# Triggy_0_2.net
KiCad netlist of a schematic drawn in EAGLE
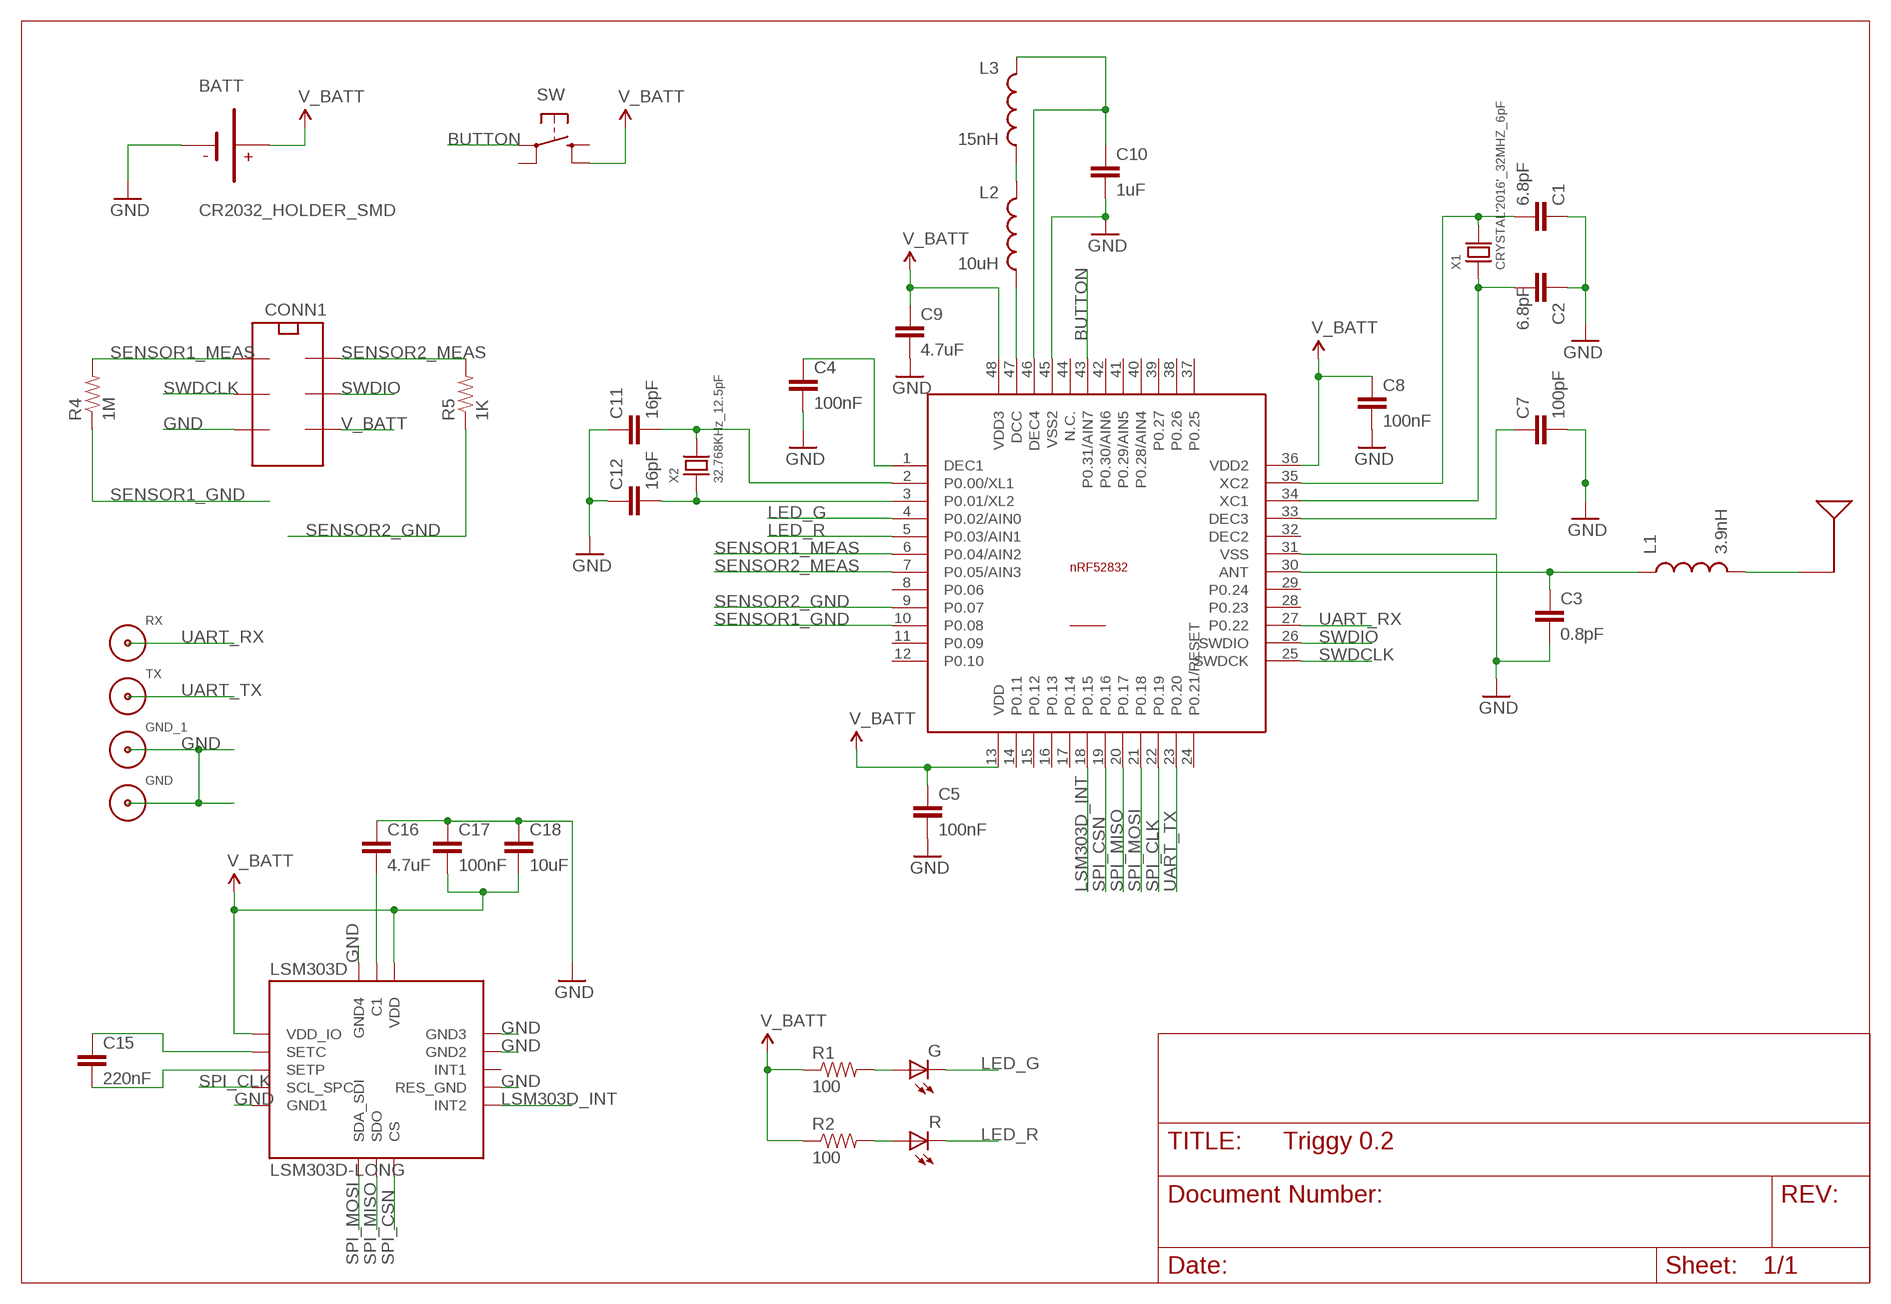
[diagram p0: schematic, sheet 1]

(export (version "E")
  (design (tool "Eeschema 10.0.6"))
  (components
    (comp (ref "ANT")
      (value "ANTENNA_2450AT43A100")
      (footprint "eagle-import:ANTENNA-SMD-7MM")
      (libsource (lib "eagle-import") (part "ANTENNA_2450AT43A100"))
    )
    (comp (ref "BATT")
      (value "CR2032_HOLDER_SMD")
      (footprint "eagle-import:CR2032_HOLDER_SMD")
      (libsource (lib "eagle-import") (part "CR2032_HOLDER_SMD"))
    )
    (comp (ref "C1")
      (value "6.8pF")
      (footprint "eagle-import:0402-CAP")
      (libsource (lib "eagle-import") (part "CAP0402-CAP"))
    )
    (comp (ref "C2")
      (value "6.8pF")
      (footprint "eagle-import:0402-CAP")
      (libsource (lib "eagle-import") (part "CAP0402-CAP"))
    )
    (comp (ref "C3")
      (value "0.8pF")
      (footprint "eagle-import:0402-CAP")
      (libsource (lib "eagle-import") (part "CAP0402-CAP"))
    )
    (comp (ref "C4")
      (value "100nF")
      (footprint "eagle-import:0402-CAP")
      (libsource (lib "eagle-import") (part "CAP0402-CAP"))
    )
    (comp (ref "C5")
      (value "100nF")
      (footprint "eagle-import:0402-CAP")
      (libsource (lib "eagle-import") (part "CAP0402-CAP"))
    )
    (comp (ref "C7")
      (value "100pF")
      (footprint "eagle-import:0402-CAP")
      (libsource (lib "eagle-import") (part "CAP0402-CAP"))
    )
    (comp (ref "C8")
      (value "100nF")
      (footprint "eagle-import:0402-CAP")
      (libsource (lib "eagle-import") (part "CAP0402-CAP"))
    )
    (comp (ref "C9")
      (value "4.7uF")
      (footprint "eagle-import:0603-CAP")
      (libsource (lib "eagle-import") (part "CAP0603-CAP"))
    )
    (comp (ref "C10")
      (value "1uF")
      (footprint "eagle-import:0603-CAP")
      (libsource (lib "eagle-import") (part "CAP0603-CAP"))
    )
    (comp (ref "C11")
      (value "16pF")
      (footprint "eagle-import:0402-CAP")
      (libsource (lib "eagle-import") (part "CAP0402-CAP"))
    )
    (comp (ref "C12")
      (value "16pF")
      (footprint "eagle-import:0402-CAP")
      (libsource (lib "eagle-import") (part "CAP0402-CAP"))
    )
    (comp (ref "C15")
      (value "220nF")
      (footprint "eagle-import:0402-CAP")
      (libsource (lib "eagle-import") (part "CAP0402-CAP"))
    )
    (comp (ref "C16")
      (value "4.7uF")
      (footprint "eagle-import:0603-CAP")
      (libsource (lib "eagle-import") (part "CAP0603-CAP"))
    )
    (comp (ref "C17")
      (value "100nF")
      (footprint "eagle-import:0402-CAP")
      (libsource (lib "eagle-import") (part "CAP0402-CAP"))
    )
    (comp (ref "C18")
      (value "10uF")
      (footprint "eagle-import:0603-CAP")
      (libsource (lib "eagle-import") (part "CAP0603-CAP"))
    )
    (comp (ref "CONN1")
      (value "MOLEX_8734006XX")
      (footprint "eagle-import:MOLEX_8734006XX")
      (libsource (lib "eagle-import") (part "MOLEX_8734006XX"))
    )
    (comp (ref "GND")
      (value "SINGLE_CONN")
      (footprint "eagle-import:SINGLE-CONN")
      (libsource (lib "eagle-import") (part "SINGLE_CONN"))
    )
    (comp (ref "GND_1")
      (value "SINGLE_CONN")
      (footprint "eagle-import:SINGLE-CONN")
      (libsource (lib "eagle-import") (part "SINGLE_CONN"))
    )
    (comp (ref "L1")
      (value "3.9nH")
      (footprint "eagle-import:C0402")
      (libsource (lib "eagle-import") (part "INDUCTOR0402"))
    )
    (comp (ref "L2")
      (value "10uH")
      (footprint "eagle-import:0603")
      (libsource (lib "eagle-import") (part "INDUCTOR0603"))
    )
    (comp (ref "L3")
      (value "15nH")
      (footprint "eagle-import:C0402")
      (libsource (lib "eagle-import") (part "INDUCTOR0402"))
    )
    (comp (ref "LEDS")
      (value "LED-R-G")
      (footprint "eagle-import:LED-RG-SMD-3X2.5MM")
      (libsource (lib "eagle-import") (part "LED-R-G"))
    )
    (comp (ref "LSM303D")
      (value "LSM303D-LONG")
      (footprint "eagle-import:LGA-16-LONG")
      (libsource (lib "eagle-import") (part "LSM303D-LONG"))
    )
    (comp (ref "NRF52832")
      (value "NRF52832_QFN")
      (footprint "eagle-import:QFN48")
      (libsource (lib "eagle-import") (part "NRF52832_QFN"))
    )
    (comp (ref "R1")
      (value "100")
      (footprint "eagle-import:0402-RES")
      (libsource (lib "eagle-import") (part "RESISTOR0402"))
    )
    (comp (ref "R2")
      (value "100")
      (footprint "eagle-import:0402-RES")
      (libsource (lib "eagle-import") (part "RESISTOR0402"))
    )
    (comp (ref "R4")
      (value "1M")
      (footprint "eagle-import:0402-RES")
      (libsource (lib "eagle-import") (part "RESISTOR0402"))
    )
    (comp (ref "R5")
      (value "1K")
      (footprint "eagle-import:0402-RES")
      (libsource (lib "eagle-import") (part "RESISTOR0402"))
    )
    (comp (ref "RX")
      (value "SINGLE_CONN")
      (footprint "eagle-import:SINGLE-CONN")
      (libsource (lib "eagle-import") (part "SINGLE_CONN"))
    )
    (comp (ref "SW")
      (value "SWITCH-PANASONIC")
      (footprint "eagle-import:SWITCH-PANASONIC")
      (libsource (lib "eagle-import") (part "SWITCH-PANASONIC"))
    )
    (comp (ref "TX")
      (value "SINGLE_CONN")
      (footprint "eagle-import:SINGLE-CONN")
      (libsource (lib "eagle-import") (part "SINGLE_CONN"))
    )
    (comp (ref "X1")
      (value "CRYSTAL'2016'_32MHZ_6pF")
      (footprint "eagle-import:X4-SMD-2.0X1.6MM")
      (libsource (lib "eagle-import") (part "CRYSTAL'2016'_32MHZ"))
    )
    (comp (ref "X2")
      (value "32.768KHz_12.5pF")
      (footprint "eagle-import:X2-SMD-3.2X1.5MM")
      (libsource (lib "eagle-import") (part "CRYSTAL'3215'"))
    )
  )
  (nets
    (net (code "1") (name "/BUTTON") (class "Default")
      (node (ref "NRF52832") (pin "43") (pinfunction "P0.31/AIN7_43") (pintype "bidirectional"))
      (node (ref "SW") (pin "A") (pinfunction "1_A") (pintype "passive"))
    )
    (net (code "2") (name "/DEC2") (class "Default")
      (node (ref "NRF52832") (pin "32") (pinfunction "DEC2_32") (pintype "power_in"))
    )
    (net (code "3") (name "/LED_G") (class "Default")
      (node (ref "LEDS") (pin "P$4") (pinfunction "P4_P$4") (pintype "passive"))
      (node (ref "NRF52832") (pin "4") (pinfunction "P0.02/AIN0_4") (pintype "bidirectional"))
    )
    (net (code "4") (name "/LED_R") (class "Default")
      (node (ref "LEDS") (pin "P$2") (pinfunction "P2_P$2") (pintype "passive"))
      (node (ref "NRF52832") (pin "5") (pinfunction "P0.03/AIN1_5") (pintype "bidirectional"))
    )
    (net (code "5") (name "/LSM303D_INT") (class "Default")
      (node (ref "LSM303D") (pin "9") (pinfunction "INT2_9") (pintype "bidirectional"))
      (node (ref "NRF52832") (pin "18") (pinfunction "P0.15_18") (pintype "bidirectional"))
    )
    (net (code "6") (name "/SENSOR1_GND") (class "Default")
      (node (ref "NRF52832") (pin "10") (pinfunction "P0.08_10") (pintype "bidirectional"))
      (node (ref "R4") (pin "1") (pinfunction "1_1") (pintype "passive"))
    )
    (net (code "7") (name "/SENSOR1_MEAS") (class "Default")
      (node (ref "CONN1") (pin "P$1") (pinfunction "P$1_P$1") (pintype "bidirectional"))
      (node (ref "NRF52832") (pin "6") (pinfunction "P0.04/AIN2_6") (pintype "bidirectional"))
      (node (ref "R4") (pin "2") (pinfunction "2_2") (pintype "passive"))
    )
    (net (code "8") (name "/SENSOR2_GND") (class "Default")
      (node (ref "NRF52832") (pin "9") (pinfunction "P0.07_9") (pintype "bidirectional"))
      (node (ref "R5") (pin "1") (pinfunction "1_1") (pintype "passive"))
    )
    (net (code "9") (name "/SENSOR2_MEAS") (class "Default")
      (node (ref "CONN1") (pin "P$2") (pinfunction "P$2_P$2") (pintype "bidirectional"))
      (node (ref "NRF52832") (pin "7") (pinfunction "P0.05/AIN3_7") (pintype "bidirectional"))
      (node (ref "R5") (pin "2") (pinfunction "2_2") (pintype "passive"))
    )
    (net (code "10") (name "/SPI_CLK") (class "Default")
      (node (ref "LSM303D") (pin "4") (pinfunction "SCL_SPC_4") (pintype "bidirectional"))
      (node (ref "NRF52832") (pin "22") (pinfunction "P0.19_22") (pintype "bidirectional"))
    )
    (net (code "11") (name "/SPI_CSN") (class "Default")
      (node (ref "LSM303D") (pin "8") (pinfunction "CS_8") (pintype "bidirectional"))
      (node (ref "NRF52832") (pin "19") (pinfunction "P0.16_19") (pintype "bidirectional"))
    )
    (net (code "12") (name "/SPI_MISO") (class "Default")
      (node (ref "LSM303D") (pin "7") (pinfunction "SDO_7") (pintype "bidirectional"))
      (node (ref "NRF52832") (pin "20") (pinfunction "P0.17_20") (pintype "bidirectional"))
    )
    (net (code "13") (name "/SPI_MOSI") (class "Default")
      (node (ref "LSM303D") (pin "6") (pinfunction "SDA_SDI_6") (pintype "bidirectional"))
      (node (ref "NRF52832") (pin "21") (pinfunction "P0.18_21") (pintype "bidirectional"))
    )
    (net (code "14") (name "/SWDCLK") (class "Default")
      (node (ref "CONN1") (pin "P$3") (pinfunction "P$3_P$3") (pintype "bidirectional"))
      (node (ref "NRF52832") (pin "25") (pinfunction "SWDCK_25") (pintype "open_collector"))
    )
    (net (code "15") (name "/SWDIO") (class "Default")
      (node (ref "CONN1") (pin "P$4") (pinfunction "P$4_P$4") (pintype "bidirectional"))
      (node (ref "NRF52832") (pin "26") (pinfunction "SWDIO_26") (pintype "bidirectional"))
    )
    (net (code "16") (name "/UART_RX") (class "Default")
      (node (ref "NRF52832") (pin "27") (pinfunction "P0.22_27") (pintype "bidirectional"))
      (node (ref "RX") (pin "1") (pinfunction "1_1") (pintype "bidirectional"))
    )
    (net (code "17") (name "/UART_TX") (class "Default")
      (node (ref "NRF52832") (pin "23") (pinfunction "P0.20_23") (pintype "bidirectional"))
      (node (ref "TX") (pin "1") (pinfunction "1_1") (pintype "bidirectional"))
    )
    (net (code "18") (name "GND") (class "Default")
      (node (ref "BATT") (pin "-") (pinfunction "-_-") (pintype "power_in"))
      (node (ref "C1") (pin "1") (pinfunction "1_1") (pintype "passive"))
      (node (ref "C10") (pin "2") (pinfunction "2_2") (pintype "passive"))
      (node (ref "C11") (pin "1") (pinfunction "1_1") (pintype "passive"))
      (node (ref "C12") (pin "1") (pinfunction "1_1") (pintype "passive"))
      (node (ref "C16") (pin "1") (pinfunction "1_1") (pintype "passive"))
      (node (ref "C17") (pin "1") (pinfunction "1_1") (pintype "passive"))
      (node (ref "C18") (pin "1") (pinfunction "1_1") (pintype "passive"))
      (node (ref "C2") (pin "1") (pinfunction "1_1") (pintype "passive"))
      (node (ref "C3") (pin "2") (pinfunction "2_2") (pintype "passive"))
      (node (ref "C4") (pin "2") (pinfunction "2_2") (pintype "passive"))
      (node (ref "C5") (pin "2") (pinfunction "2_2") (pintype "passive"))
      (node (ref "C7") (pin "2") (pinfunction "2_2") (pintype "passive"))
      (node (ref "C8") (pin "2") (pinfunction "2_2") (pintype "passive"))
      (node (ref "C9") (pin "2") (pinfunction "2_2") (pintype "passive"))
      (node (ref "CONN1") (pin "P$5") (pinfunction "P$5_P$5") (pintype "bidirectional"))
      (node (ref "GND") (pin "1") (pinfunction "1_1") (pintype "bidirectional"))
      (node (ref "GND_1") (pin "1") (pinfunction "1_1") (pintype "bidirectional"))
      (node (ref "LSM303D") (pin "10") (pinfunction "RES_GND_10") (pintype "bidirectional"))
      (node (ref "LSM303D") (pin "12") (pinfunction "GND2_12") (pintype "bidirectional"))
      (node (ref "LSM303D") (pin "13") (pinfunction "GND3_13") (pintype "bidirectional"))
      (node (ref "LSM303D") (pin "16") (pinfunction "GND4_16") (pintype "bidirectional"))
      (node (ref "LSM303D") (pin "5") (pinfunction "GND1_5") (pintype "bidirectional"))
      (node (ref "NRF52832") (pin "31") (pinfunction "VSS_31") (pintype "power_in"))
      (node (ref "NRF52832") (pin "45") (pinfunction "VSS2_45") (pintype "power_in"))
    )
    (net (code "19") (name "Net-(ANT-P$1)") (class "Default")
      (node (ref "ANT") (pin "1") (pinfunction "P$1_1") (pintype "bidirectional"))
      (node (ref "L1") (pin "2") (pinfunction "2_2") (pintype "passive"))
    )
    (net (code "20") (name "Net-(L2-Pad1)") (class "Default")
      (node (ref "L2") (pin "1") (pinfunction "1_1") (pintype "passive"))
      (node (ref "L3") (pin "2") (pinfunction "2_2") (pintype "passive"))
    )
    (net (code "21") (name "Net-(LEDS-P1)") (class "Default")
      (node (ref "LEDS") (pin "P$1") (pinfunction "P1_P$1") (pintype "passive"))
      (node (ref "R2") (pin "2") (pinfunction "2_2") (pintype "passive"))
    )
    (net (code "22") (name "Net-(LEDS-P3)") (class "Default")
      (node (ref "LEDS") (pin "P$3") (pinfunction "P3_P$3") (pintype "passive"))
      (node (ref "R1") (pin "2") (pinfunction "2_2") (pintype "passive"))
    )
    (net (code "23") (name "Net-(LSM303D-C1)") (class "Default")
      (node (ref "C16") (pin "2") (pinfunction "2_2") (pintype "passive"))
      (node (ref "LSM303D") (pin "15") (pinfunction "C1_15") (pintype "bidirectional"))
    )
    (net (code "24") (name "Net-(LSM303D-SETC)") (class "Default")
      (node (ref "C15") (pin "1") (pinfunction "1_1") (pintype "passive"))
      (node (ref "LSM303D") (pin "2") (pinfunction "SETC_2") (pintype "bidirectional"))
    )
    (net (code "25") (name "Net-(LSM303D-SETP)") (class "Default")
      (node (ref "C15") (pin "2") (pinfunction "2_2") (pintype "passive"))
      (node (ref "LSM303D") (pin "3") (pinfunction "SETP_3") (pintype "bidirectional"))
    )
    (net (code "26") (name "Net-(NRF52832-ANT)") (class "Default")
      (node (ref "C3") (pin "1") (pinfunction "1_1") (pintype "passive"))
      (node (ref "L1") (pin "1") (pinfunction "1_1") (pintype "passive"))
      (node (ref "NRF52832") (pin "30") (pinfunction "ANT_30") (pintype "bidirectional"))
    )
    (net (code "27") (name "Net-(NRF52832-DCC)") (class "Default")
      (node (ref "L2") (pin "2") (pinfunction "2_2") (pintype "passive"))
      (node (ref "NRF52832") (pin "47") (pinfunction "DCC_47") (pintype "power_in"))
    )
    (net (code "28") (name "Net-(NRF52832-DEC1)") (class "Default")
      (node (ref "C4") (pin "1") (pinfunction "1_1") (pintype "passive"))
      (node (ref "NRF52832") (pin "1") (pinfunction "DEC1_1") (pintype "power_in"))
    )
    (net (code "29") (name "Net-(NRF52832-DEC3)") (class "Default")
      (node (ref "C7") (pin "1") (pinfunction "1_1") (pintype "passive"))
      (node (ref "NRF52832") (pin "33") (pinfunction "DEC3_33") (pintype "power_in"))
    )
    (net (code "30") (name "Net-(NRF52832-DEC4)") (class "Default")
      (node (ref "C10") (pin "1") (pinfunction "1_1") (pintype "passive"))
      (node (ref "L3") (pin "1") (pinfunction "1_1") (pintype "passive"))
      (node (ref "NRF52832") (pin "46") (pinfunction "DEC4_46") (pintype "bidirectional"))
    )
    (net (code "31") (name "Net-(NRF52832-P0.00{slash}XL1)") (class "Default")
      (node (ref "C11") (pin "2") (pinfunction "2_2") (pintype "passive"))
      (node (ref "NRF52832") (pin "2") (pinfunction "P0.00/XL1_2") (pintype "bidirectional"))
      (node (ref "X2") (pin "P$2") (pinfunction "2_P$2") (pintype "passive"))
    )
    (net (code "32") (name "Net-(NRF52832-P0.01{slash}XL2)") (class "Default")
      (node (ref "C12") (pin "2") (pinfunction "2_2") (pintype "passive"))
      (node (ref "NRF52832") (pin "3") (pinfunction "P0.01/XL2_3") (pintype "bidirectional"))
      (node (ref "X2") (pin "P$1") (pinfunction "1_P$1") (pintype "passive"))
    )
    (net (code "33") (name "Net-(NRF52832-XC1)") (class "Default")
      (node (ref "C2") (pin "2") (pinfunction "2_2") (pintype "passive"))
      (node (ref "NRF52832") (pin "34") (pinfunction "XC1_34") (pintype "bidirectional"))
      (node (ref "X1") (pin "2") (pinfunction "1_2") (pintype "passive"))
    )
    (net (code "34") (name "Net-(NRF52832-XC2)") (class "Default")
      (node (ref "C1") (pin "2") (pinfunction "2_2") (pintype "passive"))
      (node (ref "NRF52832") (pin "35") (pinfunction "XC2_35") (pintype "bidirectional"))
      (node (ref "X1") (pin "4") (pinfunction "2_4") (pintype "passive"))
    )
    (net (code "35") (name "V_BATT") (class "Default")
      (node (ref "BATT") (pin "+") (pinfunction "+_+") (pintype "power_in"))
      (node (ref "BATT") (pin "+@") (pinfunction "+_+@") (pintype "power_in"))
      (node (ref "C17") (pin "2") (pinfunction "2_2") (pintype "passive"))
      (node (ref "C18") (pin "2") (pinfunction "2_2") (pintype "passive"))
      (node (ref "C5") (pin "1") (pinfunction "1_1") (pintype "passive"))
      (node (ref "C8") (pin "1") (pinfunction "1_1") (pintype "passive"))
      (node (ref "C9") (pin "1") (pinfunction "1_1") (pintype "passive"))
      (node (ref "CONN1") (pin "P$6") (pinfunction "P$6_P$6") (pintype "bidirectional"))
      (node (ref "LSM303D") (pin "1") (pinfunction "VDD_IO_1") (pintype "bidirectional"))
      (node (ref "LSM303D") (pin "14") (pinfunction "VDD_14") (pintype "bidirectional"))
      (node (ref "NRF52832") (pin "13") (pinfunction "VDD_13") (pintype "power_in"))
      (node (ref "NRF52832") (pin "36") (pinfunction "VDD2_36") (pintype "power_in"))
      (node (ref "NRF52832") (pin "48") (pinfunction "VDD3_48") (pintype "power_in"))
      (node (ref "R1") (pin "1") (pinfunction "1_1") (pintype "passive"))
      (node (ref "R2") (pin "1") (pinfunction "1_1") (pintype "passive"))
      (node (ref "SW") (pin "B'") (pinfunction "4_B'") (pintype "passive"))
    )
    (net (code "36") (name "unconnected-(LSM303D-INT1-Pad11)") (class "Default")
      (node (ref "LSM303D") (pin "11") (pinfunction "INT1_11") (pintype "bidirectional"))
    )
    (net (code "37") (name "unconnected-(NRF52832-N.C.-Pad44)") (class "Default")
      (node (ref "NRF52832") (pin "44") (pinfunction "N.C._44") (pintype "no_connect"))
    )
    (net (code "38") (name "unconnected-(NRF52832-P0.06-Pad8)") (class "Default")
      (node (ref "NRF52832") (pin "8") (pinfunction "P0.06_8") (pintype "bidirectional"))
    )
    (net (code "39") (name "unconnected-(NRF52832-P0.09-Pad11)") (class "Default")
      (node (ref "NRF52832") (pin "11") (pinfunction "P0.09_11") (pintype "bidirectional"))
    )
    (net (code "40") (name "unconnected-(NRF52832-P0.10-Pad12)") (class "Default")
      (node (ref "NRF52832") (pin "12") (pinfunction "P0.10_12") (pintype "bidirectional"))
    )
    (net (code "41") (name "unconnected-(NRF52832-P0.11-Pad14)") (class "Default")
      (node (ref "NRF52832") (pin "14") (pinfunction "P0.11_14") (pintype "bidirectional"))
    )
    (net (code "42") (name "unconnected-(NRF52832-P0.12-Pad15)") (class "Default")
      (node (ref "NRF52832") (pin "15") (pinfunction "P0.12_15") (pintype "bidirectional"))
    )
    (net (code "43") (name "unconnected-(NRF52832-P0.13-Pad16)") (class "Default")
      (node (ref "NRF52832") (pin "16") (pinfunction "P0.13_16") (pintype "bidirectional"))
    )
    (net (code "44") (name "unconnected-(NRF52832-P0.14-Pad17)") (class "Default")
      (node (ref "NRF52832") (pin "17") (pinfunction "P0.14_17") (pintype "bidirectional"))
    )
    (net (code "45") (name "unconnected-(NRF52832-P0.21{slash}RESET-Pad24)") (class "Default")
      (node (ref "NRF52832") (pin "24") (pinfunction "P0.21/RESET_24") (pintype "bidirectional"))
    )
    (net (code "46") (name "unconnected-(NRF52832-P0.23-Pad28)") (class "Default")
      (node (ref "NRF52832") (pin "28") (pinfunction "P0.23_28") (pintype "bidirectional"))
    )
    (net (code "47") (name "unconnected-(NRF52832-P0.24-Pad29)") (class "Default")
      (node (ref "NRF52832") (pin "29") (pinfunction "P0.24_29") (pintype "bidirectional"))
    )
    (net (code "48") (name "unconnected-(NRF52832-P0.25-Pad37)") (class "Default")
      (node (ref "NRF52832") (pin "37") (pinfunction "P0.25_37") (pintype "bidirectional"))
    )
    (net (code "49") (name "unconnected-(NRF52832-P0.26-Pad38)") (class "Default")
      (node (ref "NRF52832") (pin "38") (pinfunction "P0.26_38") (pintype "bidirectional"))
    )
    (net (code "50") (name "unconnected-(NRF52832-P0.27-Pad39)") (class "Default")
      (node (ref "NRF52832") (pin "39") (pinfunction "P0.27_39") (pintype "bidirectional"))
    )
    (net (code "51") (name "unconnected-(NRF52832-P0.28{slash}AIN4-Pad40)") (class "Default")
      (node (ref "NRF52832") (pin "40") (pinfunction "P0.28/AIN4_40") (pintype "bidirectional"))
    )
    (net (code "52") (name "unconnected-(NRF52832-P0.29{slash}AIN5-Pad41)") (class "Default")
      (node (ref "NRF52832") (pin "41") (pinfunction "P0.29/AIN5_41") (pintype "bidirectional"))
    )
    (net (code "53") (name "unconnected-(NRF52832-P0.30{slash}AIN6-Pad42)") (class "Default")
      (node (ref "NRF52832") (pin "42") (pinfunction "P0.30/AIN6_42") (pintype "bidirectional"))
    )
    (net (code "54") (name "unconnected-(NRF52832-SLUG-PadGND)") (class "Default")
      (node (ref "NRF52832") (pin "GND") (pinfunction "SLUG_GND") (pintype "bidirectional"))
    )
    (net (code "55") (name "unconnected-(SW-2-PadA')") (class "Default")
      (node (ref "SW") (pin "A'") (pinfunction "2_A'") (pintype "passive"))
    )
    (net (code "56") (name "unconnected-(SW-3-PadB)") (class "Default")
      (node (ref "SW") (pin "B") (pinfunction "3_B") (pintype "passive"))
    )
  )
)
